# demo2.net
KiCad netlist of a schematic drawn in EAGLE
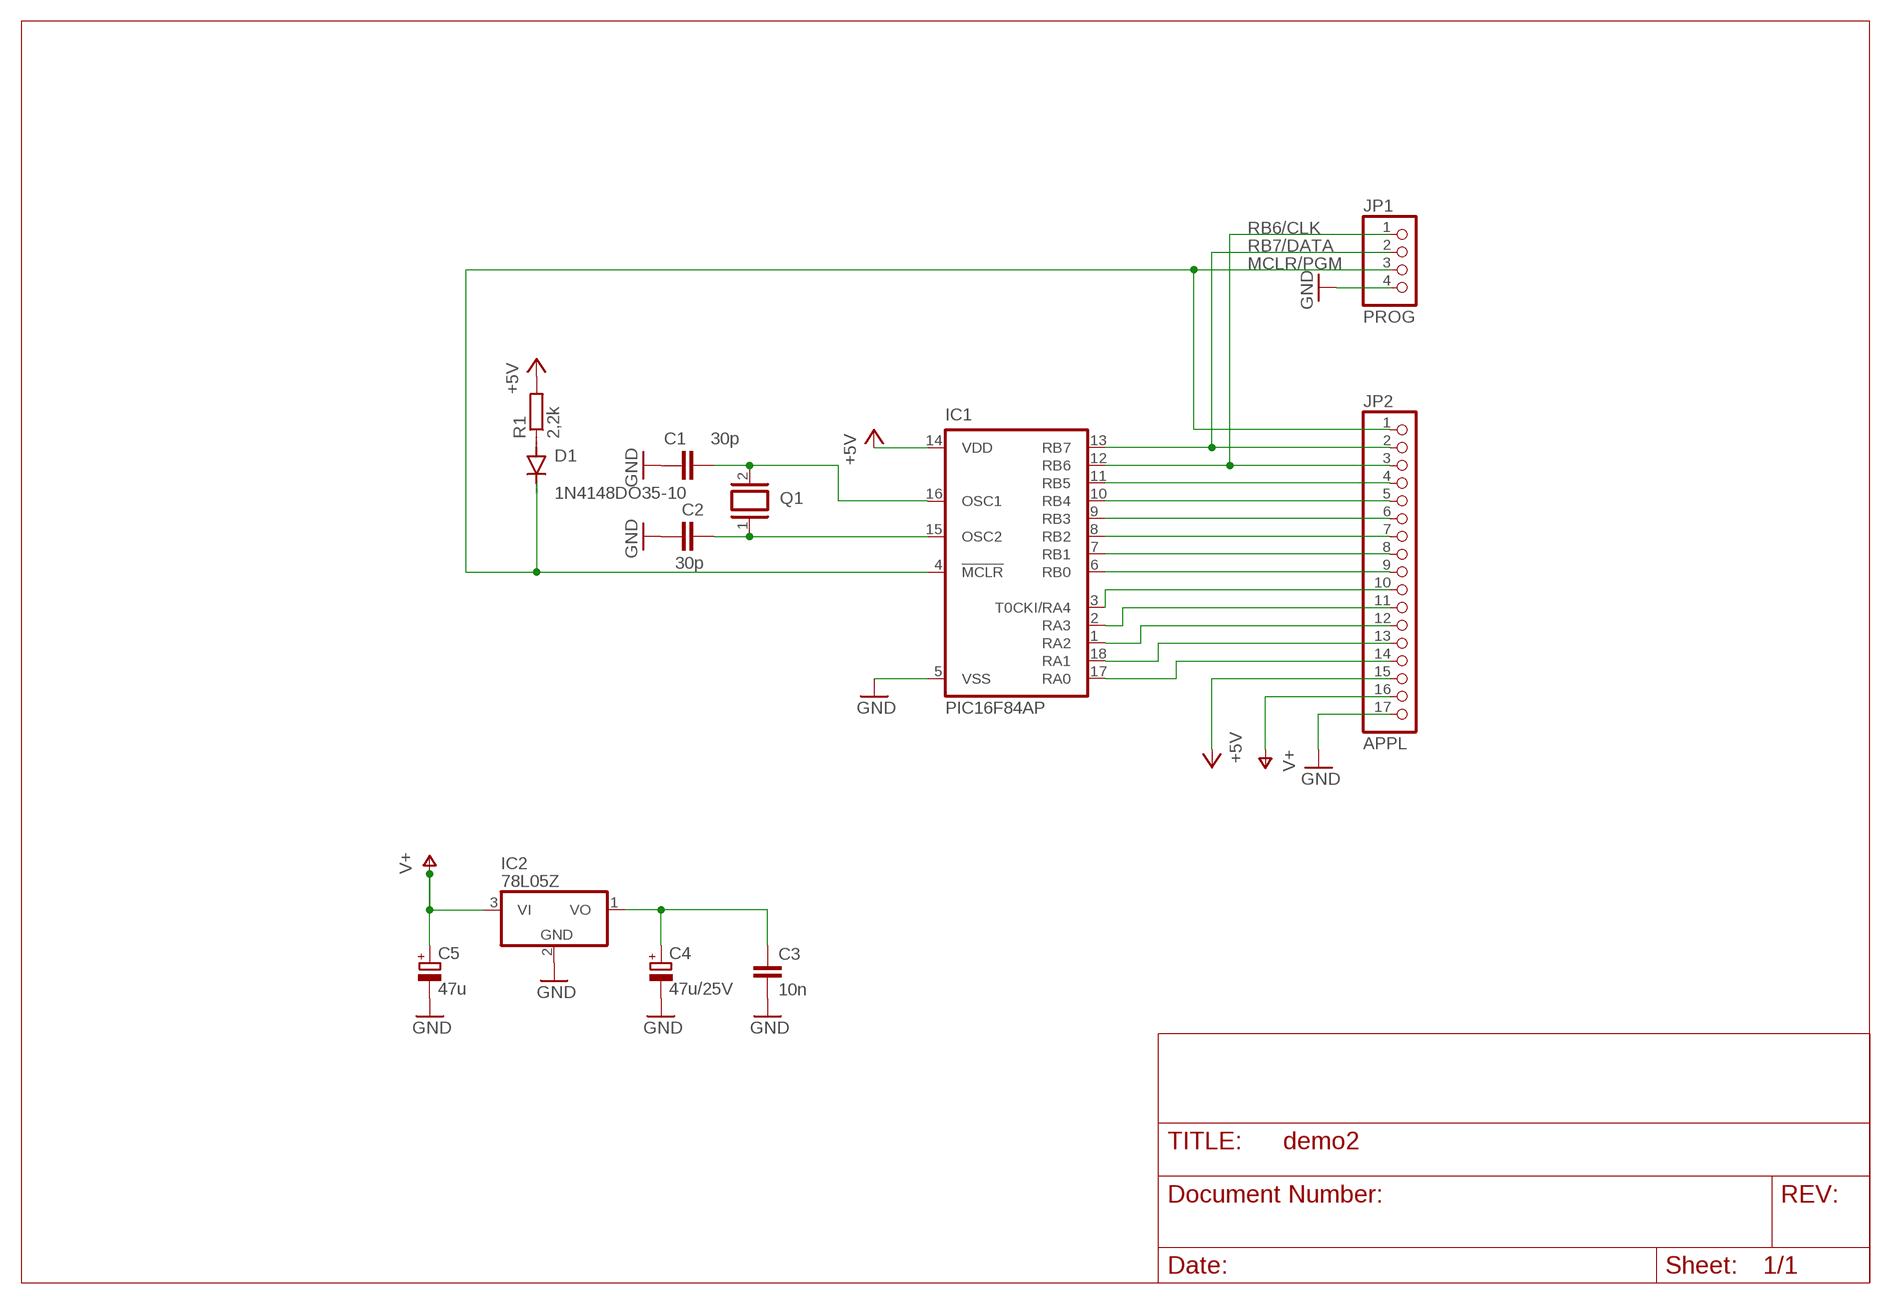
[diagram p0: schematic, sheet 1]

(export (version "E")
  (design (tool "Eeschema 10.0.6"))
  (components
    (comp (ref "C1")
      (value "30p")
      (footprint "eagle-import:C1206")
      (libsource (lib "eagle-import") (part "C-EUC1206"))
    )
    (comp (ref "C2")
      (value "30p")
      (footprint "eagle-import:C1206")
      (libsource (lib "eagle-import") (part "C-EUC1206"))
    )
    (comp (ref "C3")
      (value "10n")
      (footprint "eagle-import:C025-025X050")
      (libsource (lib "eagle-import") (part "C-EU025-025X050"))
    )
    (comp (ref "C4")
      (value "47u/25V")
      (footprint "eagle-import:TAP5-45")
      (libsource (lib "eagle-import") (part "CPOL-EUTAP5-45"))
    )
    (comp (ref "C5")
      (value "47u")
      (footprint "eagle-import:TAP5-45")
      (libsource (lib "eagle-import") (part "CPOL-EUTAP5-45"))
    )
    (comp (ref "D1")
      (value "1N4148DO35-10")
      (footprint "eagle-import:DO35-10")
      (libsource (lib "eagle-import") (part "1N4148DO35-10"))
    )
    (comp (ref "IC1")
      (value "PIC16F84AP")
      (footprint "eagle-import:DIL18")
      (fields (field (name "MF") "MICROCHIP") (field (name "MPN") "PIC16F84A-04I/P"))
      (libsource (lib "eagle-import") (part "PIC16F8P4A"))
    )
    (comp (ref "IC2")
      (value "78L05Z")
      (footprint "eagle-import:TO92")
      (libsource (lib "eagle-import") (part "78ZL05"))
    )
    (comp (ref "JP1")
      (value "PROG")
      (footprint "eagle-import:1X04")
      (libsource (lib "eagle-import") (part "PINHD-1X4"))
    )
    (comp (ref "JP2")
      (value "APPL")
      (footprint "eagle-import:1X17")
      (libsource (lib "eagle-import") (part "PINHD-1X17"))
    )
    (comp (ref "Q1")
      (value "XTAL/S")
      (footprint "eagle-import:QS")
      (libsource (lib "eagle-import") (part "XTAL/S"))
    )
    (comp (ref "R1")
      (value "2,2k")
      (footprint "eagle-import:R1206")
      (libsource (lib "eagle-import") (part "R-EU_R1206"))
    )
  )
  (nets
    (net (code "1") (name "+5V") (class "Default")
      (node (ref "IC1") (pin "14") (pinfunction "VDD_14") (pintype "power_in"))
      (node (ref "JP2") (pin "15") (pinfunction "15_15") (pintype "passive"))
      (node (ref "R1") (pin "2") (pinfunction "2_2") (pintype "passive"))
    )
    (net (code "2") (name "/MCLR{slash}PGM") (class "Default")
      (node (ref "D1") (pin "C") (pinfunction "C_C") (pintype "passive"))
      (node (ref "IC1") (pin "4") (pinfunction "~{MCLR}_4") (pintype "input"))
      (node (ref "JP1") (pin "3") (pinfunction "3_3") (pintype "passive"))
      (node (ref "JP2") (pin "1") (pinfunction "1_1") (pintype "passive"))
    )
    (net (code "3") (name "/RB6{slash}CLK") (class "Default")
      (node (ref "IC1") (pin "12") (pinfunction "RB6_12") (pintype "bidirectional"))
      (node (ref "JP1") (pin "1") (pinfunction "1_1") (pintype "passive"))
      (node (ref "JP2") (pin "3") (pinfunction "3_3") (pintype "passive"))
    )
    (net (code "4") (name "/RB7{slash}DATA") (class "Default")
      (node (ref "IC1") (pin "13") (pinfunction "RB7_13") (pintype "bidirectional"))
      (node (ref "JP1") (pin "2") (pinfunction "2_2") (pintype "passive"))
      (node (ref "JP2") (pin "2") (pinfunction "2_2") (pintype "passive"))
    )
    (net (code "5") (name "GND") (class "Default")
      (node (ref "C1") (pin "1") (pinfunction "1_1") (pintype "passive"))
      (node (ref "C2") (pin "1") (pinfunction "1_1") (pintype "passive"))
      (node (ref "C3") (pin "2") (pinfunction "2_2") (pintype "passive"))
      (node (ref "C4") (pin "-") (pinfunction "-_-") (pintype "passive"))
      (node (ref "C5") (pin "-") (pinfunction "-_-") (pintype "passive"))
      (node (ref "IC1") (pin "5") (pinfunction "VSS_5") (pintype "power_in"))
      (node (ref "IC2") (pin "2") (pinfunction "GND_2") (pintype "passive"))
      (node (ref "JP1") (pin "4") (pinfunction "4_4") (pintype "passive"))
      (node (ref "JP2") (pin "17") (pinfunction "17_17") (pintype "passive"))
    )
    (net (code "6") (name "Net-(D1-PadA)") (class "Default")
      (node (ref "D1") (pin "A") (pinfunction "A_A") (pintype "passive"))
      (node (ref "R1") (pin "1") (pinfunction "1_1") (pintype "passive"))
    )
    (net (code "7") (name "Net-(IC1-OSC1)") (class "Default")
      (node (ref "C1") (pin "2") (pinfunction "2_2") (pintype "passive"))
      (node (ref "IC1") (pin "16") (pinfunction "OSC1_16") (pintype "input"))
      (node (ref "Q1") (pin "2") (pinfunction "2_2") (pintype "passive"))
    )
    (net (code "8") (name "Net-(IC1-OSC2)") (class "Default")
      (node (ref "C2") (pin "2") (pinfunction "2_2") (pintype "passive"))
      (node (ref "IC1") (pin "15") (pinfunction "OSC2_15") (pintype "output"))
      (node (ref "Q1") (pin "1") (pinfunction "1_1") (pintype "passive"))
    )
    (net (code "9") (name "Net-(IC1-RA0)") (class "Default")
      (node (ref "IC1") (pin "17") (pinfunction "RA0_17") (pintype "bidirectional"))
      (node (ref "JP2") (pin "14") (pinfunction "14_14") (pintype "passive"))
    )
    (net (code "10") (name "Net-(IC1-RA1)") (class "Default")
      (node (ref "IC1") (pin "18") (pinfunction "RA1_18") (pintype "bidirectional"))
      (node (ref "JP2") (pin "13") (pinfunction "13_13") (pintype "passive"))
    )
    (net (code "11") (name "Net-(IC1-RA2)") (class "Default")
      (node (ref "IC1") (pin "1") (pinfunction "RA2_1") (pintype "bidirectional"))
      (node (ref "JP2") (pin "12") (pinfunction "12_12") (pintype "passive"))
    )
    (net (code "12") (name "Net-(IC1-RA3)") (class "Default")
      (node (ref "IC1") (pin "2") (pinfunction "RA3_2") (pintype "bidirectional"))
      (node (ref "JP2") (pin "11") (pinfunction "11_11") (pintype "passive"))
    )
    (net (code "13") (name "Net-(IC1-RB0)") (class "Default")
      (node (ref "IC1") (pin "6") (pinfunction "RB0_6") (pintype "bidirectional"))
      (node (ref "JP2") (pin "9") (pinfunction "9_9") (pintype "passive"))
    )
    (net (code "14") (name "Net-(IC1-RB1)") (class "Default")
      (node (ref "IC1") (pin "7") (pinfunction "RB1_7") (pintype "bidirectional"))
      (node (ref "JP2") (pin "8") (pinfunction "8_8") (pintype "passive"))
    )
    (net (code "15") (name "Net-(IC1-RB2)") (class "Default")
      (node (ref "IC1") (pin "8") (pinfunction "RB2_8") (pintype "bidirectional"))
      (node (ref "JP2") (pin "7") (pinfunction "7_7") (pintype "passive"))
    )
    (net (code "16") (name "Net-(IC1-RB3)") (class "Default")
      (node (ref "IC1") (pin "9") (pinfunction "RB3_9") (pintype "bidirectional"))
      (node (ref "JP2") (pin "6") (pinfunction "6_6") (pintype "passive"))
    )
    (net (code "17") (name "Net-(IC1-RB4)") (class "Default")
      (node (ref "IC1") (pin "10") (pinfunction "RB4_10") (pintype "bidirectional"))
      (node (ref "JP2") (pin "5") (pinfunction "5_5") (pintype "passive"))
    )
    (net (code "18") (name "Net-(IC1-RB5)") (class "Default")
      (node (ref "IC1") (pin "11") (pinfunction "RB5_11") (pintype "bidirectional"))
      (node (ref "JP2") (pin "4") (pinfunction "4_4") (pintype "passive"))
    )
    (net (code "19") (name "Net-(IC1-T0CKI{slash}RA4)") (class "Default")
      (node (ref "IC1") (pin "3") (pinfunction "T0CKI/RA4_3") (pintype "bidirectional"))
      (node (ref "JP2") (pin "10") (pinfunction "10_10") (pintype "passive"))
    )
    (net (code "20") (name "Net-(IC2-VO)") (class "Default")
      (node (ref "C3") (pin "1") (pinfunction "1_1") (pintype "passive"))
      (node (ref "C4") (pin "+") (pinfunction "+_+") (pintype "passive"))
      (node (ref "IC2") (pin "1") (pinfunction "VO_1") (pintype "passive"))
    )
    (net (code "21") (name "V+") (class "Default")
      (node (ref "C5") (pin "+") (pinfunction "+_+") (pintype "passive"))
      (node (ref "IC2") (pin "3") (pinfunction "VI_3") (pintype "input"))
      (node (ref "JP2") (pin "16") (pinfunction "16_16") (pintype "passive"))
    )
  )
)
